# pH-meter-v1-4.net
KiCad netlist of a schematic drawn in EAGLE
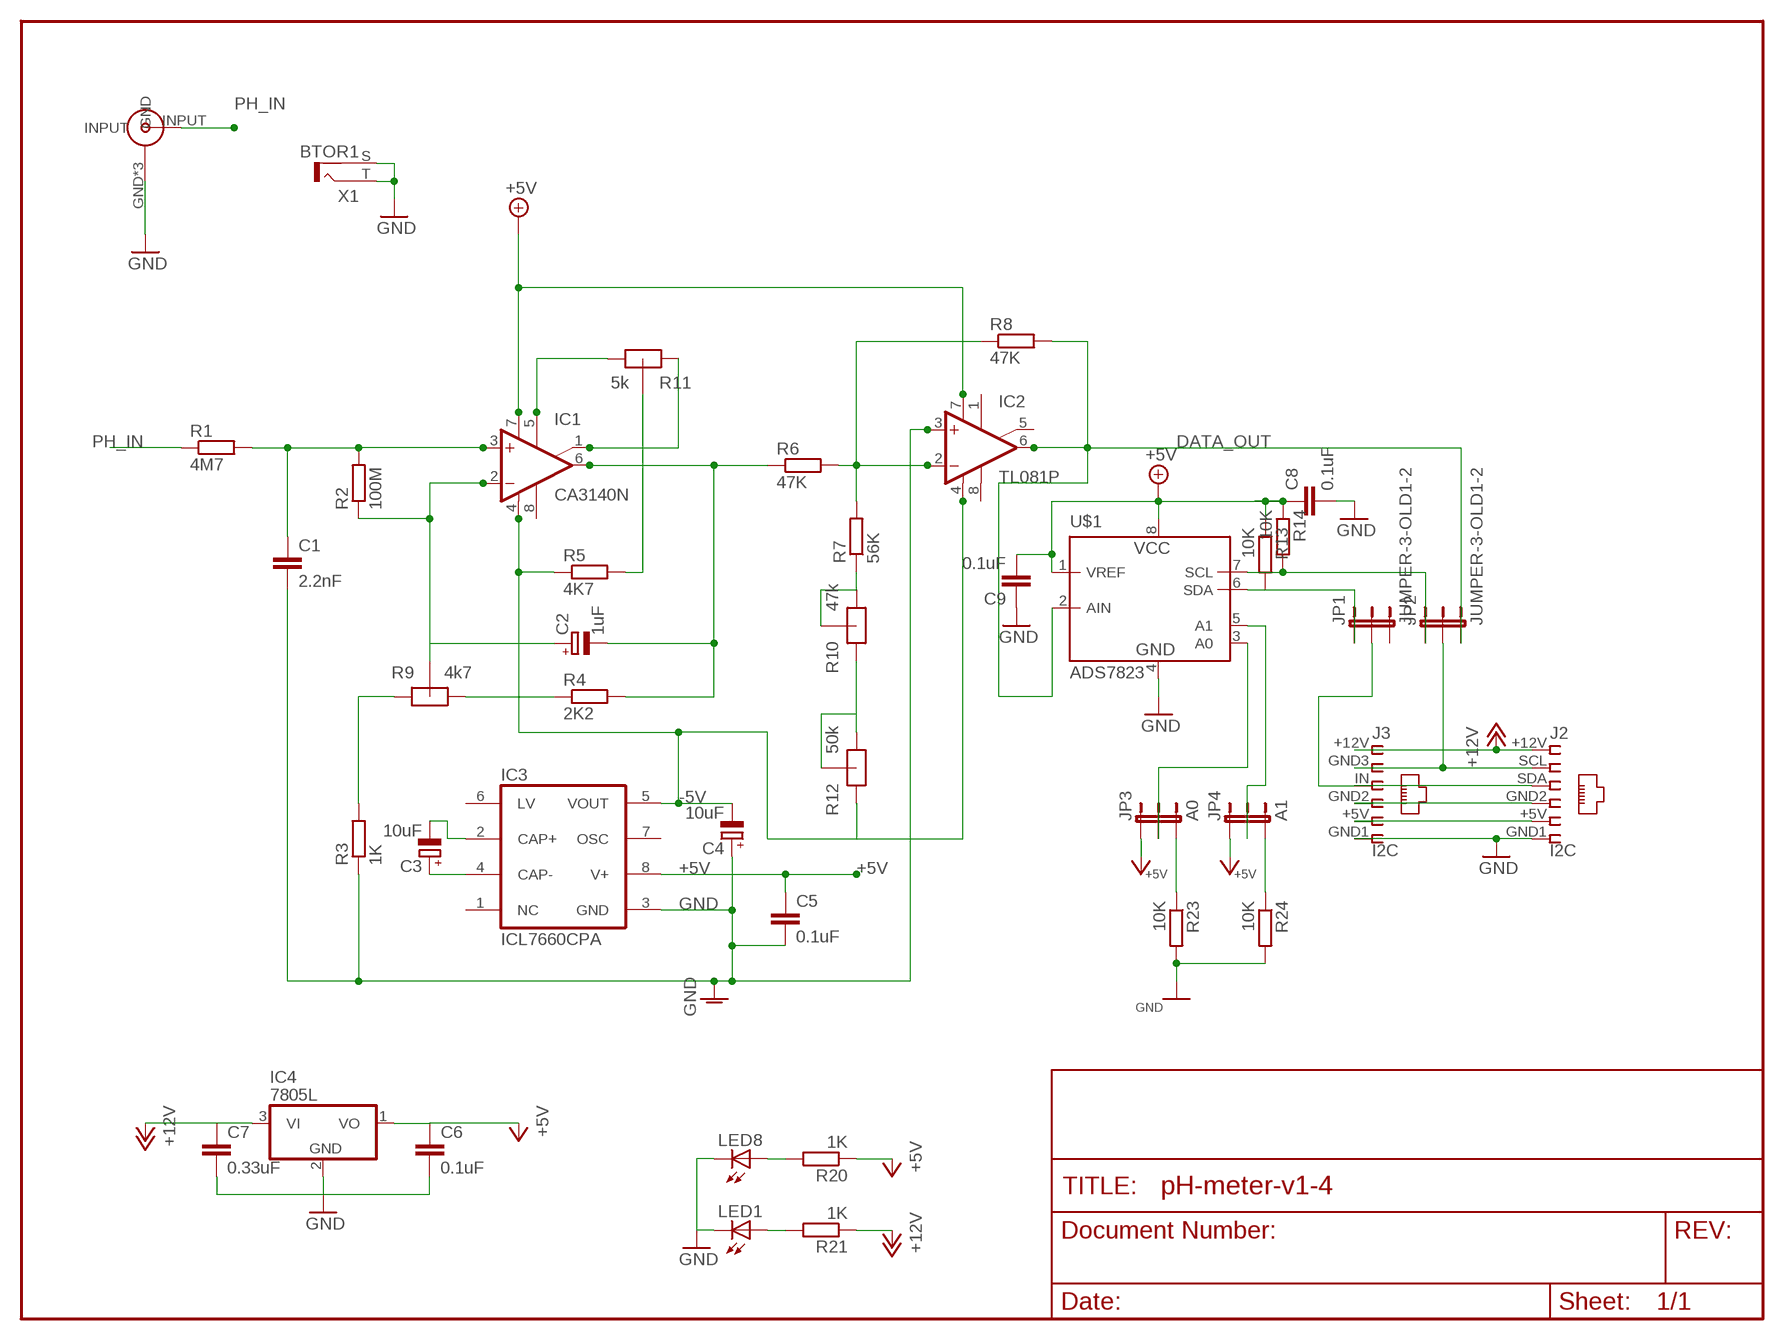
[diagram p0: schematic, sheet 1]

(export (version "E")
  (design (tool "Eeschema 10.0.6"))
  (components
    (comp (ref "C1")
      (value "2.2nF")
      (footprint "eagle-import:C025-030X050")
      (libsource (lib "eagle-import") (part "C-EU025-030X050"))
    )
    (comp (ref "C2")
      (value "1uF")
      (footprint "eagle-import:E2-4")
      (libsource (lib "eagle-import") (part "CPOL-EUE2-4"))
    )
    (comp (ref "C3")
      (value "10uF")
      (footprint "eagle-import:E2-4")
      (libsource (lib "eagle-import") (part "CPOL-EUE2-4"))
    )
    (comp (ref "C4")
      (value "10uF")
      (footprint "eagle-import:E2-4")
      (libsource (lib "eagle-import") (part "CPOL-EUE2-4"))
    )
    (comp (ref "C5")
      (value "0.1uF")
      (footprint "eagle-import:C025-030X050")
      (libsource (lib "eagle-import") (part "C-EU025-030X050"))
    )
    (comp (ref "C6")
      (value "0.1uF")
      (footprint "eagle-import:C025-030X050")
      (libsource (lib "eagle-import") (part "C-EU025-030X050"))
    )
    (comp (ref "C7")
      (value "0.33uF")
      (footprint "eagle-import:C025-030X050")
      (libsource (lib "eagle-import") (part "C-EU025-030X050"))
    )
    (comp (ref "C8")
      (value "0.1uF")
      (footprint "eagle-import:C025-030X050")
      (libsource (lib "eagle-import") (part "C-EU025-030X050"))
    )
    (comp (ref "C9")
      (value "0.1uF")
      (footprint "eagle-import:C025-030X050")
      (libsource (lib "eagle-import") (part "C-EU025-030X050"))
    )
    (comp (ref "IC1")
      (value "CA3140N")
      (footprint "eagle-import:DIL08")
      (libsource (lib "eagle-import") (part "CA3140N"))
    )
    (comp (ref "IC2")
      (value "TL081P")
      (footprint "eagle-import:DIL08")
      (libsource (lib "eagle-import") (part "TL081P"))
    )
    (comp (ref "IC3")
      (value "ICL7660CPA")
      (footprint "eagle-import:DIL08")
      (fields (field (name "MF") "INTERSIL"))
      (libsource (lib "eagle-import") (part "ICL7660CPA"))
    )
    (comp (ref "IC4")
      (value "7805L")
      (footprint "eagle-import:TO92")
      (libsource (lib "eagle-import") (part "78L05"))
    )
    (comp (ref "J2")
      (value "I2C")
      (footprint "eagle-import:RJ12-STRAIGHT-I2C")
      (libsource (lib "eagle-import") (part "RJ12STRAIGHT-I2C"))
    )
    (comp (ref "J3")
      (value "I2C")
      (footprint "eagle-import:RJ12-STRAIGHT-ANALOG")
      (libsource (lib "eagle-import") (part "RJ12STRAIGHT-ANALOG"))
    )
    (comp (ref "JP1")
      (value "JUMPER-3-OLD1-2")
      (footprint "eagle-import:SJ_3_PASTE1&2")
      (libsource (lib "eagle-import") (part "JUMPER-3-OLD1-2"))
    )
    (comp (ref "JP2")
      (value "JUMPER-3-OLD1-2")
      (footprint "eagle-import:SJ_3_PASTE1&2")
      (libsource (lib "eagle-import") (part "JUMPER-3-OLD1-2"))
    )
    (comp (ref "JP3")
      (value "A0")
      (footprint "eagle-import:SJ_3_PASTE1&2")
      (libsource (lib "eagle-import") (part "JUMPER-3-OLD1-2"))
    )
    (comp (ref "JP4")
      (value "A1")
      (footprint "eagle-import:SJ_3_PASTE1&2")
      (libsource (lib "eagle-import") (part "JUMPER-3-OLD1-2"))
    )
    (comp (ref "LED1")
      (value "LED3MM")
      (footprint "eagle-import:LED3MM")
      (libsource (lib "eagle-import") (part "LED3MM"))
    )
    (comp (ref "LED8")
      (value "LED3MM")
      (footprint "eagle-import:LED3MM")
      (libsource (lib "eagle-import") (part "LED3MM"))
    )
    (comp (ref "R1")
      (value "4M7")
      (footprint "eagle-import:0309_12")
      (libsource (lib "eagle-import") (part "R-EU_0309/12"))
    )
    (comp (ref "R2")
      (value "100M")
      (footprint "eagle-import:0309_12")
      (libsource (lib "eagle-import") (part "R-EU_0309/12"))
    )
    (comp (ref "R3")
      (value "1K")
      (footprint "eagle-import:0309_12")
      (libsource (lib "eagle-import") (part "R-EU_0309/12"))
    )
    (comp (ref "R4")
      (value "2K2")
      (footprint "eagle-import:0309_12")
      (libsource (lib "eagle-import") (part "R-EU_0309/12"))
    )
    (comp (ref "R5")
      (value "4K7")
      (footprint "eagle-import:0309_12")
      (libsource (lib "eagle-import") (part "R-EU_0309/12"))
    )
    (comp (ref "R6")
      (value "47K")
      (footprint "eagle-import:0309_12")
      (libsource (lib "eagle-import") (part "R-EU_0309/12"))
    )
    (comp (ref "R7")
      (value "56K")
      (footprint "eagle-import:0309_12")
      (libsource (lib "eagle-import") (part "R-EU_0309/12"))
    )
    (comp (ref "R8")
      (value "47K")
      (footprint "eagle-import:0309_12")
      (libsource (lib "eagle-import") (part "R-EU_0309/12"))
    )
    (comp (ref "R9")
      (value "4k7")
      (footprint "eagle-import:POT-METER_ALPS")
      (libsource (lib "eagle-import") (part "POT-METER_ALPS"))
    )
    (comp (ref "R10")
      (value "47k")
      (footprint "eagle-import:POT-METER_ALPS")
      (libsource (lib "eagle-import") (part "POT-METER_ALPS"))
    )
    (comp (ref "R11")
      (value "5k")
      (footprint "eagle-import:POT-METER_ALPS")
      (libsource (lib "eagle-import") (part "POT-METER_ALPS"))
    )
    (comp (ref "R12")
      (value "50k")
      (footprint "eagle-import:POT-METER_ALPS")
      (libsource (lib "eagle-import") (part "POT-METER_ALPS"))
    )
    (comp (ref "R13")
      (value "10K")
      (footprint "eagle-import:R1206")
      (libsource (lib "eagle-import") (part "R-EU_R1206"))
    )
    (comp (ref "R14")
      (value "10K")
      (footprint "eagle-import:R1206")
      (libsource (lib "eagle-import") (part "R-EU_R1206"))
    )
    (comp (ref "R20")
      (value "1K")
      (footprint "eagle-import:0309_12")
      (libsource (lib "eagle-import") (part "R-EU_0309/12"))
    )
    (comp (ref "R21")
      (value "1K")
      (footprint "eagle-import:0309_12")
      (libsource (lib "eagle-import") (part "R-EU_0309/12"))
    )
    (comp (ref "R23")
      (value "10K")
      (footprint "eagle-import:0309_12")
      (libsource (lib "eagle-import") (part "R-EU_0309/12"))
    )
    (comp (ref "R24")
      (value "10K")
      (footprint "eagle-import:0309_12")
      (libsource (lib "eagle-import") (part "R-EU_0309/12"))
    )
    (comp (ref "U$1")
      (value "ADS7823")
      (footprint "eagle-import:MSOP8")
      (libsource (lib "eagle-import") (part "ADS7823"))
    )
    (comp (ref "U$2")
      (value "BNC_IN")
      (footprint "eagle-import:BNC_VERTICAL_AMPHENOL")
      (libsource (lib "eagle-import") (part "BND_VERTICAL_AMPHENOL"))
    )
    (comp (ref "X1")
      (value "BTOR1")
      (footprint "eagle-import:BTOR1")
      (fields (field (name "MPN") "BTOR 1"))
      (libsource (lib "eagle-import") (part "BTOR1"))
    )
  )
  (nets
    (net (code "1") (name "+5V") (class "Default")
      (node (ref "C5") (pin "1") (pinfunction "1_1") (pintype "passive"))
      (node (ref "C6") (pin "1") (pinfunction "1_1") (pintype "passive"))
      (node (ref "C8") (pin "1") (pinfunction "1_1") (pintype "passive"))
      (node (ref "C9") (pin "2") (pinfunction "2_2") (pintype "passive"))
      (node (ref "IC1") (pin "7") (pinfunction "V+_7") (pintype "power_in"))
      (node (ref "IC2") (pin "7") (pinfunction "V+_7") (pintype "power_in"))
      (node (ref "IC3") (pin "8") (pinfunction "V+_8") (pintype "power_in"))
      (node (ref "IC4") (pin "1") (pinfunction "VO_1") (pintype "passive"))
      (node (ref "JP3") (pin "1") (pinfunction "1_1") (pintype "passive"))
      (node (ref "JP4") (pin "1") (pinfunction "1_1") (pintype "passive"))
      (node (ref "R13") (pin "1") (pinfunction "1_1") (pintype "passive"))
      (node (ref "R14") (pin "1") (pinfunction "1_1") (pintype "passive"))
      (node (ref "R20") (pin "1") (pinfunction "1_1") (pintype "passive"))
      (node (ref "U$1") (pin "1") (pinfunction "VREF_1") (pintype "input"))
      (node (ref "U$1") (pin "8") (pinfunction "VCC_8") (pintype "power_in"))
    )
    (net (code "2") (name "+12V") (class "Default")
      (node (ref "C7") (pin "1") (pinfunction "1_1") (pintype "passive"))
      (node (ref "IC4") (pin "3") (pinfunction "VI_3") (pintype "input"))
      (node (ref "J2") (pin "+12V") (pinfunction "1_+12V") (pintype "power_in"))
      (node (ref "J3") (pin "+12V") (pinfunction "1_+12V") (pintype "power_in"))
      (node (ref "R21") (pin "1") (pinfunction "1_1") (pintype "passive"))
    )
    (net (code "3") (name "/-5V") (class "Default")
      (node (ref "C4") (pin "-") (pinfunction "-_-") (pintype "passive"))
      (node (ref "IC1") (pin "4") (pinfunction "V-_4") (pintype "power_in"))
      (node (ref "IC2") (pin "4") (pinfunction "V-_4") (pintype "power_in"))
      (node (ref "IC3") (pin "5") (pinfunction "VOUT_5") (pintype "output"))
      (node (ref "R12") (pin "P$1") (pinfunction "IN_P$1") (pintype "bidirectional"))
      (node (ref "R5") (pin "1") (pinfunction "1_1") (pintype "passive"))
    )
    (net (code "4") (name "/DATA_OUT") (class "Default")
      (node (ref "IC2") (pin "6") (pinfunction "OUT_6") (pintype "output"))
      (node (ref "JP2") (pin "3") (pinfunction "3_3") (pintype "passive"))
      (node (ref "R8") (pin "2") (pinfunction "2_2") (pintype "passive"))
      (node (ref "U$1") (pin "2") (pinfunction "AIN_2") (pintype "input"))
    )
    (net (code "5") (name "/PH_IN") (class "Default")
      (node (ref "R1") (pin "1") (pinfunction "1_1") (pintype "passive"))
      (node (ref "U$2") (pin "INPUT") (pinfunction "INPUT_INPUT") (pintype "bidirectional"))
    )
    (net (code "6") (name "GND") (class "Default")
      (node (ref "C1") (pin "2") (pinfunction "2_2") (pintype "passive"))
      (node (ref "C4") (pin "+") (pinfunction "+_+") (pintype "passive"))
      (node (ref "C5") (pin "2") (pinfunction "2_2") (pintype "passive"))
      (node (ref "C6") (pin "2") (pinfunction "2_2") (pintype "passive"))
      (node (ref "C7") (pin "2") (pinfunction "2_2") (pintype "passive"))
      (node (ref "C8") (pin "2") (pinfunction "2_2") (pintype "passive"))
      (node (ref "C9") (pin "1") (pinfunction "1_1") (pintype "passive"))
      (node (ref "IC2") (pin "3") (pinfunction "+IN_3") (pintype "input"))
      (node (ref "IC3") (pin "3") (pinfunction "GND_3") (pintype "power_in"))
      (node (ref "IC4") (pin "2") (pinfunction "GND_2") (pintype "passive"))
      (node (ref "J2") (pin "GND1") (pinfunction "6_GND1") (pintype "power_in"))
      (node (ref "J2") (pin "GND2") (pinfunction "4_GND2") (pintype "power_in"))
      (node (ref "J3") (pin "GND1") (pinfunction "6_GND1") (pintype "power_in"))
      (node (ref "J3") (pin "GND2") (pinfunction "4_GND2") (pintype "power_in"))
      (node (ref "LED1") (pin "K") (pinfunction "C_K") (pintype "passive"))
      (node (ref "LED8") (pin "K") (pinfunction "C_K") (pintype "passive"))
      (node (ref "R23") (pin "2") (pinfunction "2_2") (pintype "passive"))
      (node (ref "R24") (pin "2") (pinfunction "2_2") (pintype "passive"))
      (node (ref "R3") (pin "1") (pinfunction "1_1") (pintype "passive"))
      (node (ref "U$1") (pin "4") (pinfunction "GND_4") (pintype "power_in"))
      (node (ref "U$2") (pin "GND") (pinfunction "GND_GND") (pintype "bidirectional"))
      (node (ref "U$2") (pin "GND_1") (pinfunction "GND_GND_1") (pintype "bidirectional"))
      (node (ref "U$2") (pin "GND_2") (pinfunction "GND_GND_2") (pintype "bidirectional"))
      (node (ref "X1") (pin "S") (pinfunction "2_S") (pintype "passive"))
      (node (ref "X1") (pin "T") (pinfunction "1_T") (pintype "passive"))
    )
    (net (code "7") (name "Net-(IC1-+IN)") (class "Default")
      (node (ref "C1") (pin "1") (pinfunction "1_1") (pintype "passive"))
      (node (ref "IC1") (pin "3") (pinfunction "+IN_3") (pintype "input"))
      (node (ref "R1") (pin "2") (pinfunction "2_2") (pintype "passive"))
      (node (ref "R2") (pin "2") (pinfunction "2_2") (pintype "passive"))
    )
    (net (code "8") (name "Net-(IC1--IN)") (class "Default")
      (node (ref "C2") (pin "+") (pinfunction "+_+") (pintype "passive"))
      (node (ref "IC1") (pin "2") (pinfunction "-IN_2") (pintype "input"))
      (node (ref "R2") (pin "1") (pinfunction "1_1") (pintype "passive"))
      (node (ref "R9") (pin "P$2") (pinfunction "DRIVE_P$2") (pintype "bidirectional"))
    )
    (net (code "9") (name "Net-(IC1-ON)") (class "Default")
      (node (ref "IC1") (pin "5") (pinfunction "ON_5") (pintype "passive"))
      (node (ref "R11") (pin "P$3") (pinfunction "OUT_P$3") (pintype "bidirectional"))
    )
    (net (code "10") (name "Net-(IC1-ON{slash}CMP)") (class "Default")
      (node (ref "IC1") (pin "1") (pinfunction "ON/CMP_1") (pintype "passive"))
      (node (ref "R11") (pin "P$1") (pinfunction "IN_P$1") (pintype "bidirectional"))
    )
    (net (code "11") (name "Net-(IC1-OUT)") (class "Default")
      (node (ref "C2") (pin "-") (pinfunction "-_-") (pintype "passive"))
      (node (ref "IC1") (pin "6") (pinfunction "OUT_6") (pintype "output"))
      (node (ref "R4") (pin "2") (pinfunction "2_2") (pintype "passive"))
      (node (ref "R6") (pin "1") (pinfunction "1_1") (pintype "passive"))
    )
    (net (code "12") (name "Net-(IC2--IN)") (class "Default")
      (node (ref "IC2") (pin "2") (pinfunction "-IN_2") (pintype "input"))
      (node (ref "R6") (pin "2") (pinfunction "2_2") (pintype "passive"))
      (node (ref "R7") (pin "2") (pinfunction "2_2") (pintype "passive"))
      (node (ref "R8") (pin "1") (pinfunction "1_1") (pintype "passive"))
    )
    (net (code "13") (name "Net-(IC3-CAP+)") (class "Default")
      (node (ref "C3") (pin "-") (pinfunction "-_-") (pintype "passive"))
      (node (ref "IC3") (pin "2") (pinfunction "CAP+_2") (pintype "passive"))
    )
    (net (code "14") (name "Net-(IC3-CAP-)") (class "Default")
      (node (ref "C3") (pin "+") (pinfunction "+_+") (pintype "passive"))
      (node (ref "IC3") (pin "4") (pinfunction "CAP-_4") (pintype "passive"))
    )
    (net (code "15") (name "Net-(J2-2)") (class "Default")
      (node (ref "J2") (pin "SCL") (pinfunction "2_SCL") (pintype "bidirectional"))
      (node (ref "J3") (pin "GND3") (pinfunction "2_GND3") (pintype "bidirectional"))
      (node (ref "JP2") (pin "2") (pinfunction "2_2") (pintype "passive"))
    )
    (net (code "16") (name "Net-(J2-3)") (class "Default")
      (node (ref "J2") (pin "SDA") (pinfunction "3_SDA") (pintype "bidirectional"))
      (node (ref "J3") (pin "IN") (pinfunction "3_IN") (pintype "bidirectional"))
      (node (ref "JP1") (pin "2") (pinfunction "2_2") (pintype "passive"))
    )
    (net (code "17") (name "Net-(J2-5)") (class "Default")
      (node (ref "J2") (pin "+5V") (pinfunction "5_+5V") (pintype "power_in"))
      (node (ref "J3") (pin "+5V") (pinfunction "5_+5V") (pintype "power_in"))
    )
    (net (code "18") (name "Net-(JP3-Pad3)") (class "Default")
      (node (ref "JP3") (pin "3") (pinfunction "3_3") (pintype "passive"))
      (node (ref "R23") (pin "1") (pinfunction "1_1") (pintype "passive"))
    )
    (net (code "19") (name "Net-(JP4-Pad3)") (class "Default")
      (node (ref "JP4") (pin "3") (pinfunction "3_3") (pintype "passive"))
      (node (ref "R24") (pin "1") (pinfunction "1_1") (pintype "passive"))
    )
    (net (code "20") (name "Net-(LED1-PadA)") (class "Default")
      (node (ref "LED1") (pin "A") (pinfunction "A_A") (pintype "passive"))
      (node (ref "R21") (pin "2") (pinfunction "2_2") (pintype "passive"))
    )
    (net (code "21") (name "Net-(LED8-PadA)") (class "Default")
      (node (ref "LED8") (pin "A") (pinfunction "A_A") (pintype "passive"))
      (node (ref "R20") (pin "2") (pinfunction "2_2") (pintype "passive"))
    )
    (net (code "22") (name "Net-(R9-IN)") (class "Default")
      (node (ref "R3") (pin "2") (pinfunction "2_2") (pintype "passive"))
      (node (ref "R9") (pin "P$1") (pinfunction "IN_P$1") (pintype "bidirectional"))
    )
    (net (code "23") (name "Net-(R9-OUT)") (class "Default")
      (node (ref "R4") (pin "1") (pinfunction "1_1") (pintype "passive"))
      (node (ref "R9") (pin "P$3") (pinfunction "OUT_P$3") (pintype "bidirectional"))
    )
    (net (code "24") (name "Net-(R10-DRIVE)") (class "Default")
      (node (ref "R10") (pin "P$2") (pinfunction "DRIVE_P$2") (pintype "bidirectional"))
      (node (ref "R10") (pin "P$3") (pinfunction "OUT_P$3") (pintype "bidirectional"))
      (node (ref "R7") (pin "1") (pinfunction "1_1") (pintype "passive"))
    )
    (net (code "25") (name "Net-(R10-IN)") (class "Default")
      (node (ref "R10") (pin "P$1") (pinfunction "IN_P$1") (pintype "bidirectional"))
      (node (ref "R12") (pin "P$2") (pinfunction "DRIVE_P$2") (pintype "bidirectional"))
      (node (ref "R12") (pin "P$3") (pinfunction "OUT_P$3") (pintype "bidirectional"))
    )
    (net (code "26") (name "Net-(R11-DRIVE)") (class "Default")
      (node (ref "R11") (pin "P$2") (pinfunction "DRIVE_P$2") (pintype "bidirectional"))
      (node (ref "R5") (pin "2") (pinfunction "2_2") (pintype "passive"))
    )
    (net (code "27") (name "Net-(U$1-A0)") (class "Default")
      (node (ref "JP3") (pin "2") (pinfunction "2_2") (pintype "passive"))
      (node (ref "U$1") (pin "3") (pinfunction "A0_3") (pintype "input"))
    )
    (net (code "28") (name "Net-(U$1-A1)") (class "Default")
      (node (ref "JP4") (pin "2") (pinfunction "2_2") (pintype "passive"))
      (node (ref "U$1") (pin "5") (pinfunction "A1_5") (pintype "input"))
    )
    (net (code "29") (name "Net-(U$1-SCL)") (class "Default")
      (node (ref "JP2") (pin "1") (pinfunction "1_1") (pintype "passive"))
      (node (ref "R14") (pin "2") (pinfunction "2_2") (pintype "passive"))
      (node (ref "U$1") (pin "7") (pinfunction "SCL_7") (pintype "input"))
    )
    (net (code "30") (name "Net-(U$1-SDA)") (class "Default")
      (node (ref "JP1") (pin "1") (pinfunction "1_1") (pintype "passive"))
      (node (ref "R13") (pin "2") (pinfunction "2_2") (pintype "passive"))
      (node (ref "U$1") (pin "6") (pinfunction "SDA_6") (pintype "bidirectional"))
    )
    (net (code "31") (name "unconnected-(IC1-CMP-Pad8)") (class "Default")
      (node (ref "IC1") (pin "8") (pinfunction "CMP_8") (pintype "passive"))
    )
    (net (code "32") (name "unconnected-(IC2-ON1-Pad1)") (class "Default")
      (node (ref "IC2") (pin "1") (pinfunction "ON1_1") (pintype "passive"))
    )
    (net (code "33") (name "unconnected-(IC2-ON2-Pad5)") (class "Default")
      (node (ref "IC2") (pin "5") (pinfunction "ON2_5") (pintype "passive"))
    )
    (net (code "34") (name "unconnected-(IC2-OPT-Pad8)") (class "Default")
      (node (ref "IC2") (pin "8") (pinfunction "OPT_8") (pintype "passive"))
    )
    (net (code "35") (name "unconnected-(IC3-LV-Pad6)") (class "Default")
      (node (ref "IC3") (pin "6") (pinfunction "LV_6") (pintype "passive"))
    )
    (net (code "36") (name "unconnected-(IC3-NC-Pad1)") (class "Default")
      (node (ref "IC3") (pin "1") (pinfunction "NC_1") (pintype "no_connect"))
    )
    (net (code "37") (name "unconnected-(IC3-OSC-Pad7)") (class "Default")
      (node (ref "IC3") (pin "7") (pinfunction "OSC_7") (pintype "output"))
    )
    (net (code "38") (name "unconnected-(JP1-Pad3)") (class "Default")
      (node (ref "JP1") (pin "3") (pinfunction "3_3") (pintype "passive"))
    )
    (net (code "39") (name "unconnected-(X1-2-PadS@1)") (class "Default")
      (node (ref "X1") (pin "S@1") (pinfunction "2_S@1") (pintype "passive"))
    )
    (net (code "40") (name "unconnected-(X1-2-PadS@2)") (class "Default")
      (node (ref "X1") (pin "S@2") (pinfunction "2_S@2") (pintype "passive"))
    )
    (net (code "41") (name "unconnected-(X1-2-PadS@3)") (class "Default")
      (node (ref "X1") (pin "S@3") (pinfunction "2_S@3") (pintype "passive"))
    )
  )
)
